# buck1.net
KiCad netlist of a schematic drawn in Altium Designer
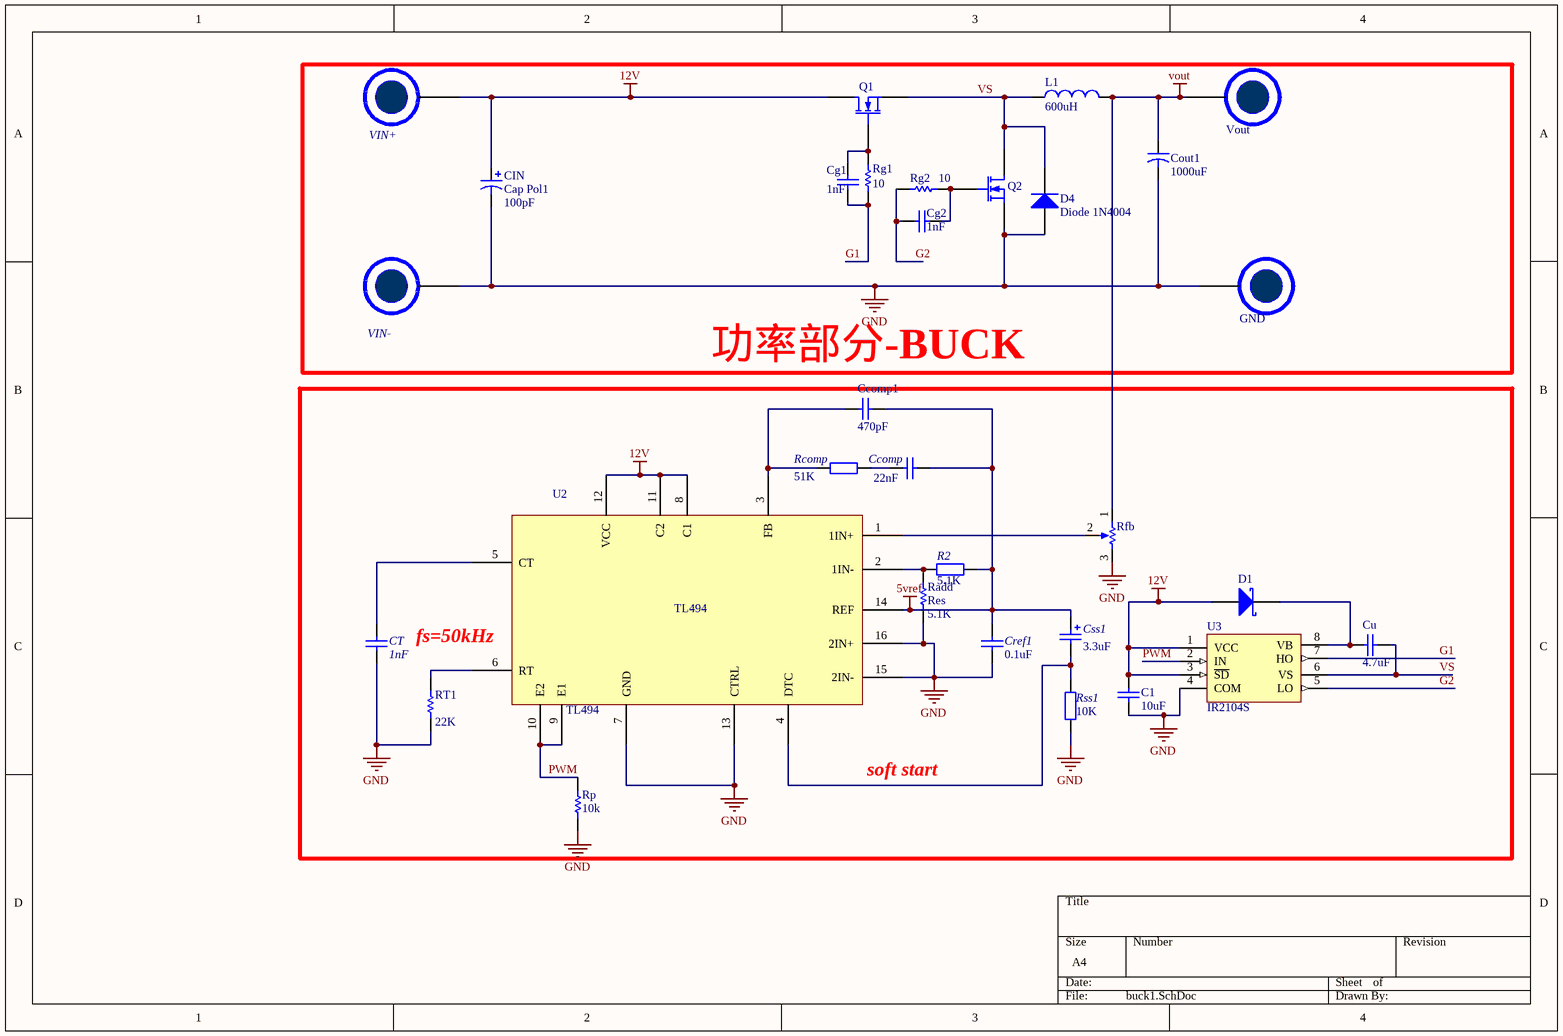
[diagram p0: buck1.SchDoc]

(export (version "E")
  (design (tool "Eeschema 10.0.6"))
  (components
    (comp (ref "C1")
      (value "10uF")
      (footprint "1206(2)")
      (description "Capacitor")
      (fields (field (name "Comment") "Cap") (field (name "PUBLISHER") "Altium Limited"))
      (libsource (lib "Miscellaneous Devices") (part "Cap"))
    )
    (comp (ref "Ccomp")
      (value "22nF")
      (footprint "C2012")
      (description "0.1uF 0805")
      (fields (field (name "PUBLISHER") "Altium Limited"))
      (libsource (lib "常用元件库") (part "----Cap"))
    )
    (comp (ref "Ccomp1")
      (value "470pF")
      (footprint "C2012")
      (description "Capacitor")
      (fields (field (name "Comment") "Cap") (field (name "PUBLISHER") "Altium Limited"))
      (libsource (lib "Miscellaneous Devices") (part "Cap"))
    )
    (comp (ref "Cg1")
      (value "1nF")
      (footprint "1206(2)")
      (description "Capacitor")
      (fields (field (name "Comment") "Cap") (field (name "PUBLISHER") "Altium Limited"))
      (libsource (lib "Miscellaneous Devices") (part "Cap"))
    )
    (comp (ref "Cg2")
      (value "1nF")
      (footprint "1206(2)")
      (description "Capacitor")
      (fields (field (name "Comment") "Cap") (field (name "PUBLISHER") "Altium Limited"))
      (libsource (lib "Miscellaneous Devices") (part "Cap"))
    )
    (comp (ref "CIN")
      (value "Cap Pol1")
      (footprint "RB7.6-15")
      (description "Polarized Capacitor (Radial)")
      (fields (field (name "ALTIUM_VALUE") "100pF") (field (name "PUBLISHER") "Altium Limited"))
      (libsource (lib "Miscellaneous Devices") (part "Cap Pol1"))
    )
    (comp (ref "Cout1")
      (value "1000uF")
      (footprint "RB7.6-15")
      (description "Capacitor")
      (fields (field (name "Comment") "Cap2") (field (name "PUBLISHER") "Altium Limited"))
      (libsource (lib "Miscellaneous Devices") (part "Cap2"))
    )
    (comp (ref "Cref1")
      (value "0.1uF")
      (footprint "C2012")
      (description "0.1uF 0805")
      (fields (field (name "PUBLISHER") "Altium Limited"))
      (libsource (lib "常用元件库") (part "----Cap"))
    )
    (comp (ref "Css1")
      (value "3.3uF")
      (footprint "C2012")
      (description "10uF RAD0.1_")
      (fields (field (name "PUBLISHER") "Altium Limited"))
      (libsource (lib "常用元件库") (part "----Cap Pol1"))
    )
    (comp (ref "CT")
      (value "1nF")
      (footprint "C2012")
      (description "0.1uF 0805")
      (fields (field (name "PUBLISHER") "Altium Limited"))
      (libsource (lib "常用元件库") (part "----Cap"))
    )
    (comp (ref "Cu")
      (value "4.7uF")
      (footprint "1206(2)")
      (description "Capacitor")
      (fields (field (name "Comment") "Cap") (field (name "PUBLISHER") "Altium Limited"))
      (libsource (lib "Miscellaneous Devices") (part "Cap"))
    )
    (comp (ref "D1")
      (value "D Schottky")
      (footprint "SK54")
      (description "Schottky Diode")
      (fields (field (name "PUBLISHER") "Altium Limited"))
      (libsource (lib "Miscellaneous Devices") (part "D Schottky"))
    )
    (comp (ref "D4")
      (value "Diode 1N4004")
      (footprint "SK54")
      (description "1 Amp General Purpose Rectifier")
      (fields (field (name "PUBLISHER") "Altium Limited"))
      (libsource (lib "Miscellaneous Devices") (part "Diode 1N4004"))
    )
    (comp (ref "GND") (value "PIN") (footprint "PIN") (libsource (lib "常用元件库") (part "PIN")))
    (comp (ref "L1")
      (value "600uH")
      (footprint "AXIAL-1.0")
      (description "Inductor")
      (fields (field (name "PUBLISHER") "Altium Limited"))
      (libsource (lib "Miscellaneous Devices") (part "Inductor"))
    )
    (comp (ref "Q1")
      (value "MOSFET-N")
      (footprint "nmos")
      (description "N-Channel MOSFET")
      (fields (field (name "PUBLISHER") "Altium Limited"))
      (libsource (lib "Miscellaneous Devices") (part "MOSFET-N"))
    )
    (comp (ref "Q2")
      (value "MOSFET-N")
      (footprint "nmos")
      (description "N-Channel MOSFET")
      (fields (field (name "PUBLISHER") "Altium Limited"))
      (libsource (lib "Miscellaneous Devices") (part "MOSFET-N"))
    )
    (comp (ref "R2")
      (value "5.1K")
      (footprint "R2012")
      (description "0805_")
      (fields (field (name "PUBLISHER") "Altium Limited"))
      (libsource (lib "") (part "---Res1_1"))
    )
    (comp (ref "Radd")
      (value "Res")
      (footprint "R2012")
      (description "贴片电阻")
      (fields (field (name "ALTIUM_VALUE") "5.1K") (field (name "PUBLISHER") "Altium Limited"))
      (libsource (lib "Sparks") (part "Res"))
    )
    (comp (ref "Rcomp")
      (value "51K")
      (footprint "R2012")
      (description "0805_")
      (fields (field (name "PUBLISHER") "Altium Limited"))
      (libsource (lib "常用元件库") (part "---Res1"))
    )
    (comp (ref "Rfb")
      (value "100k")
      (footprint "pot（长方形）")
      (description "Potentiometer")
      (fields (field (name "PUBLISHER") "Altium Limited"))
      (libsource (lib "常用元件库") (part "RPot"))
    )
    (comp (ref "Rg1")
      (value "10")
      (footprint "1206(2)")
      (description "Resistor")
      (fields (field (name "Comment") "Res1") (field (name "PUBLISHER") "Altium Limited"))
      (libsource (lib "Miscellaneous Devices") (part "Res1"))
    )
    (comp (ref "Rg2")
      (value "10")
      (footprint "1206(2)")
      (description "Resistor")
      (fields (field (name "Comment") "Res1") (field (name "PUBLISHER") "Altium Limited"))
      (libsource (lib "Miscellaneous Devices") (part "Res1"))
    )
    (comp (ref "Rp")
      (value "10k")
      (footprint "1206(2)")
      (description "Resistor")
      (fields (field (name "Comment") "Res1") (field (name "PUBLISHER") "Altium Limited"))
      (libsource (lib "Miscellaneous Devices") (part "Res1"))
    )
    (comp (ref "Rss1")
      (value "10K")
      (footprint "R2012")
      (description "0805_")
      (fields (field (name "PUBLISHER") "Altium Limited"))
      (libsource (lib "") (part "---Res1_2"))
    )
    (comp (ref "RT1")
      (value "22K")
      (footprint "R2012")
      (description "贴片电阻")
      (fields (field (name "Comment") "Res") (field (name "PUBLISHER") "Altium Limited"))
      (libsource (lib "Sparks") (part "Res"))
    )
    (comp (ref "U2") (value "TL494") (footprint "DIP-16") (libsource (lib "Schlib1") (part "TL494")))
    (comp (ref "U3")
      (value "IR2104S")
      (footprint "ir2104")
      (description "High and Low Side Driver")
      (fields (field (name "PUBLISHER") "Altium Limited"))
      (libsource (lib "IR Interface Bridge Driver") (part "IR2104S"))
    )
    (comp (ref "VIN+") (value "PIN") (footprint "PIN") (libsource (lib "常用元件库") (part "PIN")))
    (comp (ref "VIN-") (value "PIN") (footprint "PIN") (libsource (lib "常用元件库") (part "PIN")))
    (comp (ref "Vout") (value "PIN") (footprint "PIN") (libsource (lib "常用元件库") (part "PIN")))
  )
  (nets
    (net (code "1") (name "/G1") (class "Default")
      (node (ref "Cg1") (pin "1") (pinfunction "1_1") (pintype "passive"))
      (node (ref "Rg1") (pin "1") (pinfunction "1_1") (pintype "passive"))
      (node (ref "U3") (pin "7") (pinfunction "HO_7") (pintype "output"))
    )
    (net (code "2") (name "/G2") (class "Default")
      (node (ref "Cg2") (pin "2") (pinfunction "2_2") (pintype "passive"))
      (node (ref "Rg2") (pin "2") (pinfunction "2_2") (pintype "passive"))
      (node (ref "U3") (pin "5") (pinfunction "LO_5") (pintype "output"))
    )
    (net (code "3") (name "/PWM") (class "Default")
      (node (ref "Rp") (pin "2") (pinfunction "2_2") (pintype "passive"))
      (node (ref "U2") (pin "10") (pinfunction "E2_10") (pintype "passive"))
      (node (ref "U2") (pin "9") (pinfunction "E1_9") (pintype "passive"))
      (node (ref "U3") (pin "2") (pinfunction "IN_2") (pintype "input"))
    )
    (net (code "4") (name "/VS") (class "Default")
      (node (ref "Cu") (pin "1") (pinfunction "1_1") (pintype "passive"))
      (node (ref "D4") (pin "2") (pinfunction "K_2") (pintype "passive"))
      (node (ref "L1") (pin "1") (pinfunction "1_1") (pintype "passive"))
      (node (ref "Q1") (pin "3") (pinfunction "S_3") (pintype "passive"))
      (node (ref "Q2") (pin "2") (pinfunction "D_2") (pintype "passive"))
      (node (ref "U3") (pin "6") (pinfunction "VS_6") (pintype "power_in"))
    )
    (net (code "5") (name "5vref") (class "Default")
      (node (ref "Ccomp") (pin "2") (pinfunction "2_2") (pintype "passive"))
      (node (ref "Ccomp1") (pin "1") (pinfunction "1_1") (pintype "passive"))
      (node (ref "Cref1") (pin "2") (pinfunction "2_2") (pintype "passive"))
      (node (ref "Css1") (pin "1") (pinfunction "1_1") (pintype "passive"))
      (node (ref "R2") (pin "2") (pinfunction "2_2") (pintype "passive"))
      (node (ref "U2") (pin "14") (pinfunction "REF_14") (pintype "passive"))
    )
    (net (code "6") (name "12V") (class "Default")
      (node (ref "C1") (pin "1") (pinfunction "1_1") (pintype "passive"))
      (node (ref "CIN") (pin "1") (pinfunction "1_1") (pintype "passive"))
      (node (ref "D1") (pin "1") (pinfunction "A_1") (pintype "passive"))
      (node (ref "Q1") (pin "2") (pinfunction "D_2") (pintype "passive"))
      (node (ref "U2") (pin "11") (pinfunction "C2_11") (pintype "passive"))
      (node (ref "U2") (pin "12") (pinfunction "VCC_12") (pintype "passive"))
      (node (ref "U2") (pin "8") (pinfunction "C1_8") (pintype "passive"))
      (node (ref "U3") (pin "1") (pinfunction "VCC_1") (pintype "power_in"))
      (node (ref "U3") (pin "3") (pinfunction "~{SD}_3") (pintype "input"))
      (node (ref "VIN+") (pin "1") (pinfunction "PIN_1") (pintype "passive"))
    )
    (net (code "7") (name "GND") (class "Default")
      (node (ref "C1") (pin "2") (pinfunction "2_2") (pintype "passive"))
      (node (ref "CIN") (pin "2") (pinfunction "2_2") (pintype "passive"))
      (node (ref "CT") (pin "1") (pinfunction "1_1") (pintype "passive"))
      (node (ref "Cout1") (pin "2") (pinfunction "2_2") (pintype "passive"))
      (node (ref "Cref1") (pin "1") (pinfunction "1_1") (pintype "passive"))
      (node (ref "D4") (pin "1") (pinfunction "A_1") (pintype "passive"))
      (node (ref "GND") (pin "1") (pinfunction "PIN_1") (pintype "passive"))
      (node (ref "Q2") (pin "3") (pinfunction "S_3") (pintype "passive"))
      (node (ref "RT1") (pin "1") (pinfunction "1_1") (pintype "passive"))
      (node (ref "Radd") (pin "1") (pinfunction "1_1") (pintype "passive"))
      (node (ref "Rfb") (pin "3") (pinfunction "BOT_3") (pintype "passive"))
      (node (ref "Rp") (pin "1") (pinfunction "1_1") (pintype "passive"))
      (node (ref "Rss1") (pin "1") (pinfunction "1_1") (pintype "passive"))
      (node (ref "U2") (pin "13") (pinfunction "CTRL_13") (pintype "passive"))
      (node (ref "U2") (pin "15") (pinfunction "2IN-_15") (pintype "passive"))
      (node (ref "U2") (pin "16") (pinfunction "2IN+_16") (pintype "passive"))
      (node (ref "U2") (pin "7") (pinfunction "GND_7") (pintype "passive"))
      (node (ref "U3") (pin "4") (pinfunction "COM_4") (pintype "power_in"))
      (node (ref "VIN-") (pin "1") (pinfunction "PIN_1") (pintype "passive"))
    )
    (net (code "8") (name "Net-(Ccomp-Pad1)") (class "Default")
      (node (ref "Ccomp") (pin "1") (pinfunction "1_1") (pintype "passive"))
      (node (ref "Rcomp") (pin "1") (pinfunction "1_1") (pintype "passive"))
    )
    (net (code "9") (name "Net-(D1-K)") (class "Default")
      (node (ref "Cu") (pin "2") (pinfunction "2_2") (pintype "passive"))
      (node (ref "D1") (pin "2") (pinfunction "K_2") (pintype "passive"))
      (node (ref "U3") (pin "8") (pinfunction "VB_8") (pintype "power_in"))
    )
    (net (code "10") (name "Net-(Q1-G)") (class "Default")
      (node (ref "Cg1") (pin "2") (pinfunction "2_2") (pintype "passive"))
      (node (ref "Q1") (pin "1") (pinfunction "G_1") (pintype "passive"))
      (node (ref "Rg1") (pin "2") (pinfunction "2_2") (pintype "passive"))
    )
    (net (code "11") (name "Net-(Q2-G)") (class "Default")
      (node (ref "Cg2") (pin "1") (pinfunction "1_1") (pintype "passive"))
      (node (ref "Q2") (pin "1") (pinfunction "G_1") (pintype "passive"))
      (node (ref "Rg2") (pin "1") (pinfunction "1_1") (pintype "passive"))
    )
    (net (code "12") (name "Net-(Rfb-TAP)") (class "Default")
      (node (ref "Rfb") (pin "2") (pinfunction "TAP_2") (pintype "passive"))
      (node (ref "U2") (pin "1") (pinfunction "1IN+_1") (pintype "passive"))
    )
    (net (code "13") (name "Net-(U2-1IN-)") (class "Default")
      (node (ref "R2") (pin "1") (pinfunction "1_1") (pintype "passive"))
      (node (ref "Radd") (pin "2") (pinfunction "2_2") (pintype "passive"))
      (node (ref "U2") (pin "2") (pinfunction "1IN-_2") (pintype "passive"))
    )
    (net (code "14") (name "Net-(U2-CT)") (class "Default")
      (node (ref "CT") (pin "2") (pinfunction "2_2") (pintype "passive"))
      (node (ref "U2") (pin "5") (pinfunction "CT_5") (pintype "passive"))
    )
    (net (code "15") (name "Net-(U2-DTC)") (class "Default")
      (node (ref "Css1") (pin "2") (pinfunction "2_2") (pintype "passive"))
      (node (ref "Rss1") (pin "2") (pinfunction "2_2") (pintype "passive"))
      (node (ref "U2") (pin "4") (pinfunction "DTC_4") (pintype "passive"))
    )
    (net (code "16") (name "Net-(U2-FB)") (class "Default")
      (node (ref "Ccomp1") (pin "2") (pinfunction "2_2") (pintype "passive"))
      (node (ref "Rcomp") (pin "2") (pinfunction "2_2") (pintype "passive"))
      (node (ref "U2") (pin "3") (pinfunction "FB_3") (pintype "passive"))
    )
    (net (code "17") (name "Net-(U2-RT)") (class "Default")
      (node (ref "RT1") (pin "2") (pinfunction "2_2") (pintype "passive"))
      (node (ref "U2") (pin "6") (pinfunction "RT_6") (pintype "passive"))
    )
    (net (code "18") (name "vout") (class "Default")
      (node (ref "Cout1") (pin "1") (pinfunction "1_1") (pintype "passive"))
      (node (ref "L1") (pin "2") (pinfunction "2_2") (pintype "passive"))
      (node (ref "Rfb") (pin "1") (pinfunction "TOP_1") (pintype "passive"))
      (node (ref "Vout") (pin "1") (pinfunction "PIN_1") (pintype "passive"))
    )
  )
)
